# JustSensor.net
KiCad netlist of a schematic drawn in EAGLE
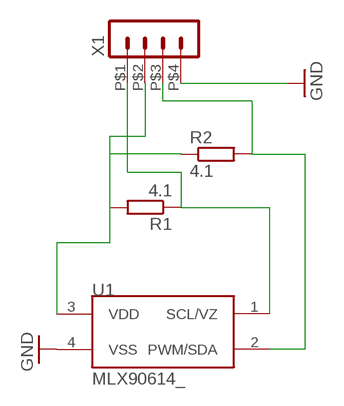
[diagram p0: schematic, sheet 1]

(export (version "E")
  (design (tool "Eeschema 10.0.6"))
  (components
    (comp (ref "R1")
      (value "4.1")
      (footprint "eagle-import:0204_7")
      (libsource (lib "eagle-import") (part "R-EU_0204/7"))
    )
    (comp (ref "R2")
      (value "4.1")
      (footprint "eagle-import:0204_7")
      (libsource (lib "eagle-import") (part "R-EU_0204/7"))
    )
    (comp (ref "U1")
      (value "MLX90614_")
      (footprint "eagle-import:TO-39")
      (libsource (lib "eagle-import") (part "MLX90614_"))
    )
    (comp (ref "X1")
      (value "HEADER_POS4_43045-0401")
      (footprint "eagle-import:43045-0400")
      (libsource (lib "eagle-import") (part "HEADER_POS4_?43045-0401"))
    )
  )
  (nets
    (net (code "1") (name "GND") (class "Default")
      (node (ref "U1") (pin "4") (pinfunction "VSS_4") (pintype "bidirectional"))
      (node (ref "X1") (pin "P$4") (pinfunction "4_P$4") (pintype "passive"))
    )
    (net (code "2") (name "Net-(U1-PWM{slash}SDA)") (class "Default")
      (node (ref "R2") (pin "2") (pinfunction "2_2") (pintype "passive"))
      (node (ref "U1") (pin "2") (pinfunction "PWM/SDA_2") (pintype "bidirectional"))
      (node (ref "X1") (pin "P$3") (pinfunction "3_P$3") (pintype "passive"))
    )
    (net (code "3") (name "Net-(U1-SCL{slash}VZ)") (class "Default")
      (node (ref "R1") (pin "1") (pinfunction "1_1") (pintype "passive"))
      (node (ref "U1") (pin "1") (pinfunction "SCL/VZ_1") (pintype "bidirectional"))
      (node (ref "X1") (pin "P$1") (pinfunction "1_P$1") (pintype "passive"))
    )
    (net (code "4") (name "Net-(U1-VDD)") (class "Default")
      (node (ref "R1") (pin "2") (pinfunction "2_2") (pintype "passive"))
      (node (ref "R2") (pin "1") (pinfunction "1_1") (pintype "passive"))
      (node (ref "U1") (pin "3") (pinfunction "VDD_3") (pintype "bidirectional"))
      (node (ref "X1") (pin "P$2") (pinfunction "2_P$2") (pintype "passive"))
    )
  )
)
